# HeatpumpMonitor.net
KiCad netlist of a schematic drawn in EAGLE
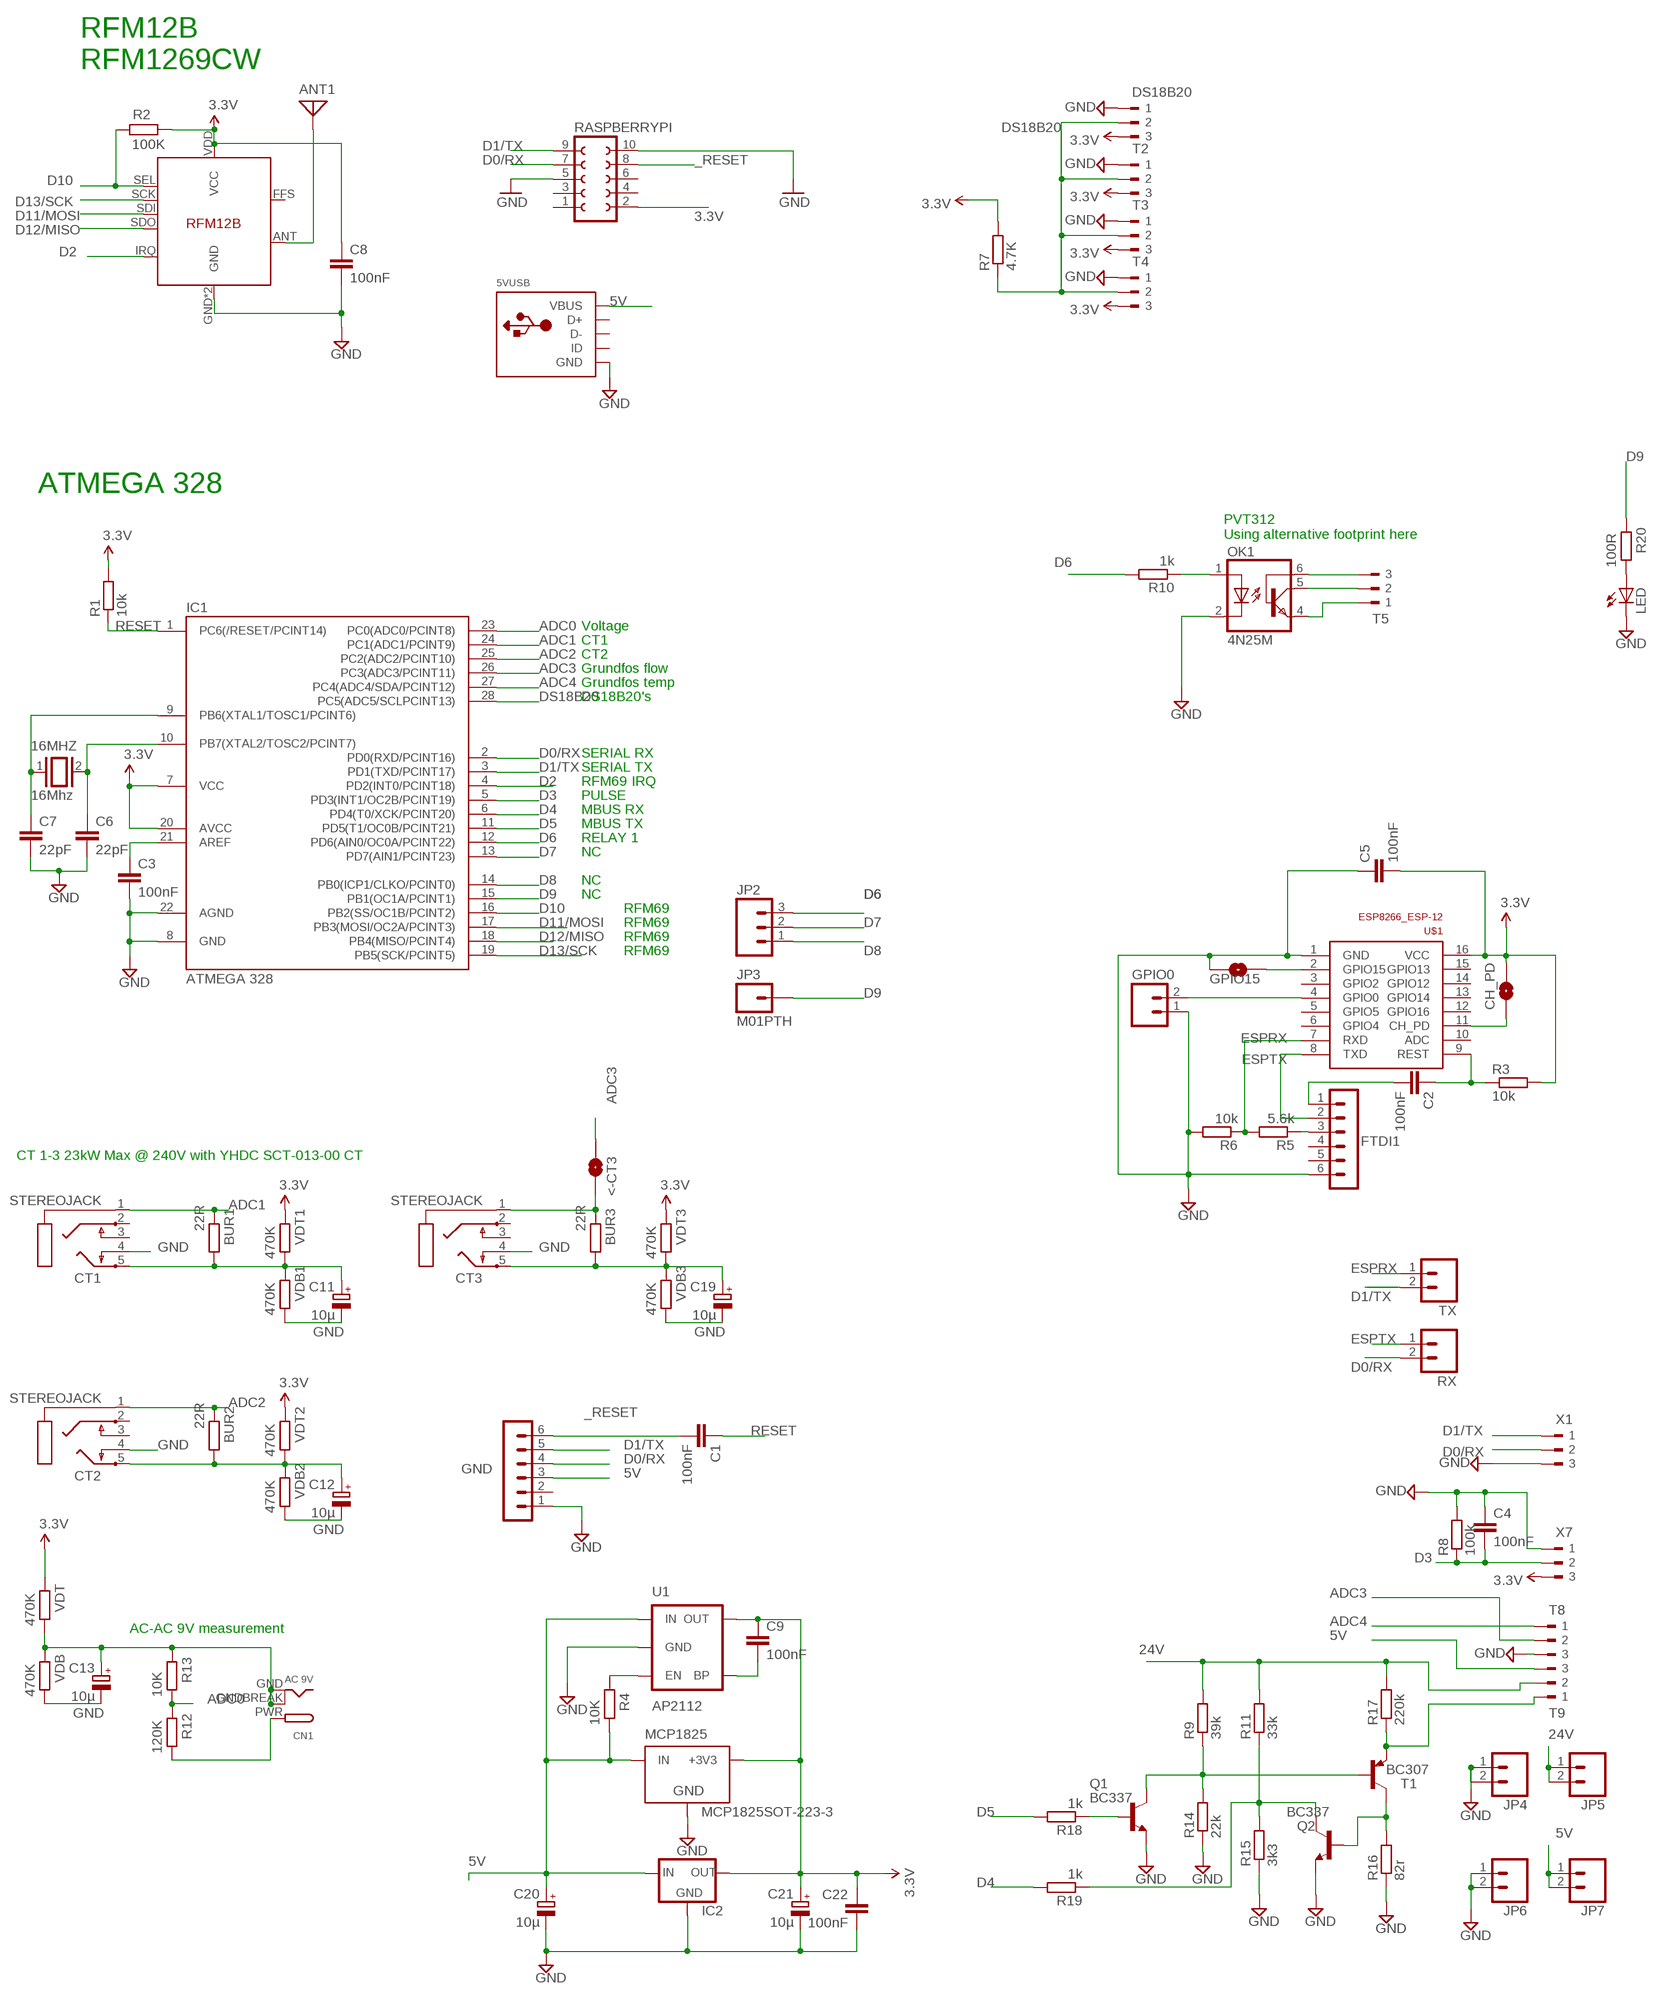
[diagram p0: schematic, sheet 1]

(export (version "E")
  (design (tool "Eeschema 10.0.6"))
  (components
    (comp (ref "5VUSB")
      (value "USBMOLEX")
      (footprint "eagle-import:USB-MINIB-THM-MOLEX")
      (libsource (lib "eagle-import") (part "USBMOLEX"))
    )
    (comp (ref "16MHZ")
      (value "16Mhz")
      (footprint "eagle-import:QS")
      (libsource (lib "eagle-import") (part "XTAL/S"))
    )
    (comp (ref "<-CT3")
      (value "SOLDERJUMPERNO")
      (footprint "eagle-import:SJ_2S-NO")
      (libsource (lib "eagle-import") (part "SOLDERJUMPERNO"))
    )
    (comp (ref "ANT1")
      (value "ANTENNA")
      (footprint "eagle-import:PAD-01")
      (libsource (lib "eagle-import") (part "ANTENNA"))
    )
    (comp (ref "BUR1")
      (value "22R")
      (footprint "eagle-import:0204_7")
      (libsource (lib "eagle-import") (part "R-EU_0204/7"))
    )
    (comp (ref "BUR2")
      (value "22R")
      (footprint "eagle-import:0204_7")
      (libsource (lib "eagle-import") (part "R-EU_0204/7"))
    )
    (comp (ref "BUR3")
      (value "22R")
      (footprint "eagle-import:0204_7")
      (libsource (lib "eagle-import") (part "R-EU_0204/7"))
    )
    (comp (ref "C1")
      (value "100nF")
      (footprint "eagle-import:C025-024X044")
      (libsource (lib "eagle-import") (part "C-EU025-024X044"))
    )
    (comp (ref "C2")
      (value "100nF")
      (footprint "eagle-import:C025-024X044")
      (libsource (lib "eagle-import") (part "C-EU025-024X044"))
    )
    (comp (ref "C3")
      (value "100nF")
      (footprint "eagle-import:C025-024X044")
      (libsource (lib "eagle-import") (part "C-EU025-024X044"))
    )
    (comp (ref "C4")
      (value "100nF")
      (footprint "eagle-import:C025-024X044")
      (libsource (lib "eagle-import") (part "C-EU025-024X044"))
    )
    (comp (ref "C5")
      (value "100nF")
      (footprint "eagle-import:C025-024X044")
      (libsource (lib "eagle-import") (part "C-EU025-024X044"))
    )
    (comp (ref "C6")
      (value "22pF")
      (footprint "eagle-import:C2.5-2")
      (libsource (lib "eagle-import") (part "C2.5/2"))
    )
    (comp (ref "C7")
      (value "22pF")
      (footprint "eagle-import:C2.5-2")
      (libsource (lib "eagle-import") (part "C2.5/2"))
    )
    (comp (ref "C8")
      (value "100nF")
      (footprint "eagle-import:C025-024X044")
      (libsource (lib "eagle-import") (part "C-EU025-024X044"))
    )
    (comp (ref "C9")
      (value "100nF")
      (footprint "eagle-import:C0603")
      (libsource (lib "eagle-import") (part "C-EUC0603"))
    )
    (comp (ref "C11")
      (value "10µ")
      (footprint "eagle-import:E1,8-4")
      (libsource (lib "eagle-import") (part "CPOL-EUE1.8-4"))
    )
    (comp (ref "C12")
      (value "10µ")
      (footprint "eagle-import:E1,8-4")
      (libsource (lib "eagle-import") (part "CPOL-EUE1.8-4"))
    )
    (comp (ref "C13")
      (value "10µ")
      (footprint "eagle-import:E1,8-4")
      (libsource (lib "eagle-import") (part "CPOL-EUE1.8-4"))
    )
    (comp (ref "C19")
      (value "10µ")
      (footprint "eagle-import:E1,8-4")
      (libsource (lib "eagle-import") (part "CPOL-EUE1.8-4"))
    )
    (comp (ref "C20")
      (value "10µ")
      (footprint "eagle-import:E1,8-4")
      (libsource (lib "eagle-import") (part "CPOL-EUE1.8-4"))
    )
    (comp (ref "C21")
      (value "10µ")
      (footprint "eagle-import:E1,8-4")
      (libsource (lib "eagle-import") (part "CPOL-EUE1.8-4"))
    )
    (comp (ref "C22")
      (value "100nF")
      (footprint "eagle-import:C025-024X044")
      (libsource (lib "eagle-import") (part "C-EU025-024X044"))
    )
    (comp (ref "CH_PD")
      (value "SOLDERJUMPERNO")
      (footprint "eagle-import:SJ_2S-NO")
      (libsource (lib "eagle-import") (part "SOLDERJUMPERNO"))
    )
    (comp (ref "CN1")
      (value "AC 9V")
      (footprint "eagle-import:DCJACK_2MM_PTH")
      (libsource (lib "eagle-import") (part "DCBARRELPTH"))
    )
    (comp (ref "CT1")
      (value "STEREOJACK")
      (footprint "eagle-import:STX3100")
      (libsource (lib "eagle-import") (part "STEREOJACK"))
    )
    (comp (ref "CT2")
      (value "STEREOJACK")
      (footprint "eagle-import:STX3100")
      (libsource (lib "eagle-import") (part "STEREOJACK"))
    )
    (comp (ref "CT3")
      (value "STEREOJACK")
      (footprint "eagle-import:STX3100")
      (libsource (lib "eagle-import") (part "STEREOJACK"))
    )
    (comp (ref "DS18B20")
      (value "180-3")
      (footprint "eagle-import:180-3")
      (libsource (lib "eagle-import") (part "180-3"))
    )
    (comp (ref "FTDI1")
      (value "FTDI")
      (footprint "eagle-import:MA06-1")
      (libsource (lib "eagle-import") (part "MA06-1"))
    )
    (comp (ref "GND")
      (value "FTDI")
      (footprint "eagle-import:MA06-1")
      (libsource (lib "eagle-import") (part "MA06-1"))
    )
    (comp (ref "GPIO0")
      (value "M02PTH")
      (footprint "eagle-import:1X02")
      (libsource (lib "eagle-import") (part "M02PTH"))
    )
    (comp (ref "GPIO15")
      (value "SOLDERJUMPERNO")
      (footprint "eagle-import:SJ_2S-NO")
      (libsource (lib "eagle-import") (part "SOLDERJUMPERNO"))
    )
    (comp (ref "IC1")
      (value "ATMEGA 328")
      (footprint "eagle-import:DIL28-3")
      (libsource (lib "eagle-import") (part "ATMEGA48/88/168-PU"))
    )
    (comp (ref "IC2")
      (value "78XXS")
      (footprint "eagle-import:78XXS")
      (libsource (lib "eagle-import") (part "78XXS"))
    )
    (comp (ref "JP2")
      (value "M03PTH")
      (footprint "eagle-import:1X03")
      (libsource (lib "eagle-import") (part "M03PTH"))
    )
    (comp (ref "JP3")
      (value "M01PTH")
      (footprint "eagle-import:1X01")
      (libsource (lib "eagle-import") (part "M01PTH"))
    )
    (comp (ref "JP4")
      (value "M02PTH")
      (footprint "eagle-import:1X02")
      (libsource (lib "eagle-import") (part "M02PTH"))
    )
    (comp (ref "JP5")
      (value "M02PTH")
      (footprint "eagle-import:1X02")
      (libsource (lib "eagle-import") (part "M02PTH"))
    )
    (comp (ref "JP6")
      (value "M02PTH")
      (footprint "eagle-import:1X02")
      (libsource (lib "eagle-import") (part "M02PTH"))
    )
    (comp (ref "JP7")
      (value "M02PTH")
      (footprint "eagle-import:1X02")
      (libsource (lib "eagle-import") (part "M02PTH"))
    )
    (comp (ref "LED")
      (value "LED3MM")
      (footprint "eagle-import:LED3MM")
      (libsource (lib "eagle-import") (part "LED3MM"))
    )
    (comp (ref "MCP1825")
      (value "MCP1825SOT-223-3")
      (footprint "eagle-import:SOT-223")
      (libsource (lib "eagle-import") (part "MCP1825SOT-223-3"))
    )
    (comp (ref "OK1")
      (value "4N25M")
      (footprint "eagle-import:DIL06")
      (fields (field (name "MPN") "4N25-M"))
      (libsource (lib "eagle-import") (part "4N?M25"))
    )
    (comp (ref "Q1")
      (value "BC337")
      (footprint "eagle-import:TO92")
      (libsource (lib "eagle-import") (part "BC337"))
    )
    (comp (ref "Q2")
      (value "BC337")
      (footprint "eagle-import:TO92")
      (libsource (lib "eagle-import") (part "BC337"))
    )
    (comp (ref "R1")
      (value "10k")
      (footprint "eagle-import:0204_7")
      (libsource (lib "eagle-import") (part "resistor_R-EU_0204/7"))
    )
    (comp (ref "R2")
      (value "100K")
      (footprint "eagle-import:0204_7")
      (libsource (lib "eagle-import") (part "R-EU_0204/7"))
    )
    (comp (ref "R3")
      (value "10k")
      (footprint "eagle-import:0204_7")
      (libsource (lib "eagle-import") (part "R-EU_0204/7"))
    )
    (comp (ref "R4")
      (value "10K")
      (footprint "eagle-import:R0603")
      (libsource (lib "eagle-import") (part "R-EU_R0603"))
    )
    (comp (ref "R5")
      (value "5.6k")
      (footprint "eagle-import:0204_7")
      (libsource (lib "eagle-import") (part "R-EU_0204/7"))
    )
    (comp (ref "R6")
      (value "10k")
      (footprint "eagle-import:0204_7")
      (libsource (lib "eagle-import") (part "R-EU_0204/7"))
    )
    (comp (ref "R7")
      (value "4.7K")
      (footprint "eagle-import:0204_7")
      (libsource (lib "eagle-import") (part "resistor_R-EU_0204/7"))
    )
    (comp (ref "R8")
      (value "100k")
      (footprint "eagle-import:0207_2V")
      (libsource (lib "eagle-import") (part "R-EU_0207/2V"))
    )
    (comp (ref "R9")
      (value "39k")
      (footprint "eagle-import:0204_7")
      (libsource (lib "eagle-import") (part "resistor_R-EU_0204/7"))
    )
    (comp (ref "R10")
      (value "1k")
      (footprint "eagle-import:0204_7")
      (libsource (lib "eagle-import") (part "R-EU_0204/7"))
    )
    (comp (ref "R11")
      (value "33k")
      (footprint "eagle-import:0204_7")
      (libsource (lib "eagle-import") (part "resistor_R-EU_0204/7"))
    )
    (comp (ref "R12")
      (value "120K")
      (footprint "eagle-import:0204_7")
      (libsource (lib "eagle-import") (part "R-EU_0204/7"))
    )
    (comp (ref "R13")
      (value "10K")
      (footprint "eagle-import:0204_7")
      (libsource (lib "eagle-import") (part "R-EU_0204/7"))
    )
    (comp (ref "R14")
      (value "22k")
      (footprint "eagle-import:0204_7")
      (libsource (lib "eagle-import") (part "resistor_R-EU_0204/7"))
    )
    (comp (ref "R15")
      (value "3k3")
      (footprint "eagle-import:0204_7")
      (libsource (lib "eagle-import") (part "resistor_R-EU_0204/7"))
    )
    (comp (ref "R16")
      (value "82r")
      (footprint "eagle-import:0204_7")
      (libsource (lib "eagle-import") (part "resistor_R-EU_0204/7"))
    )
    (comp (ref "R17")
      (value "220k")
      (footprint "eagle-import:0204_7")
      (libsource (lib "eagle-import") (part "resistor_R-EU_0204/7"))
    )
    (comp (ref "R18")
      (value "1k")
      (footprint "eagle-import:0204_7")
      (libsource (lib "eagle-import") (part "resistor_R-EU_0204/7"))
    )
    (comp (ref "R19")
      (value "1k")
      (footprint "eagle-import:0204_7")
      (libsource (lib "eagle-import") (part "resistor_R-EU_0204/7"))
    )
    (comp (ref "R20")
      (value "100R")
      (footprint "eagle-import:0204_7")
      (libsource (lib "eagle-import") (part "R-EU_0204/7"))
    )
    (comp (ref "RASPBERRYPI")
      (value "FE05-2")
      (footprint "eagle-import:FE05-2")
      (libsource (lib "eagle-import") (part "FE05-2"))
    )
    (comp (ref "RX")
      (value "M02PTH")
      (footprint "eagle-import:1X02")
      (libsource (lib "eagle-import") (part "M02PTH"))
    )
    (comp (ref "T1")
      (value "BC307")
      (footprint "eagle-import:TO92")
      (libsource (lib "eagle-import") (part "BC307"))
    )
    (comp (ref "T2")
      (value "180-3")
      (footprint "eagle-import:180-3")
      (libsource (lib "eagle-import") (part "180-3"))
    )
    (comp (ref "T3")
      (value "180-3")
      (footprint "eagle-import:180-3")
      (libsource (lib "eagle-import") (part "180-3"))
    )
    (comp (ref "T4")
      (value "180-3")
      (footprint "eagle-import:180-3")
      (libsource (lib "eagle-import") (part "180-3"))
    )
    (comp (ref "T5")
      (value "180-3")
      (footprint "eagle-import:180-3")
      (libsource (lib "eagle-import") (part "180-3"))
    )
    (comp (ref "T8")
      (value "180-3")
      (footprint "eagle-import:180-3")
      (libsource (lib "eagle-import") (part "180-3"))
    )
    (comp (ref "T9")
      (value "180-3")
      (footprint "eagle-import:180-3")
      (libsource (lib "eagle-import") (part "180-3"))
    )
    (comp (ref "TX")
      (value "M02PTH")
      (footprint "eagle-import:1X02")
      (libsource (lib "eagle-import") (part "M02PTH"))
    )
    (comp (ref "U$1")
      (value "ESP8266_ESP-12")
      (footprint "eagle-import:ESP8266-ESP12")
      (libsource (lib "eagle-import") (part "ESP8266_ESP-12"))
    )
    (comp (ref "U$14")
      (value "RFM12B")
      (footprint "eagle-import:RFM12B")
      (libsource (lib "eagle-import") (part "RFM12B"))
    )
    (comp (ref "U1")
      (value "AP2112")
      (footprint "eagle-import:SOT23-5")
      (libsource (lib "eagle-import") (part "V_REG_LDOSMD"))
    )
    (comp (ref "VDB")
      (value "470K")
      (footprint "eagle-import:0204_7")
      (libsource (lib "eagle-import") (part "R-EU_0204/7"))
    )
    (comp (ref "VDB1")
      (value "470K")
      (footprint "eagle-import:0204_7")
      (libsource (lib "eagle-import") (part "R-EU_0204/7"))
    )
    (comp (ref "VDB2")
      (value "470K")
      (footprint "eagle-import:0204_7")
      (libsource (lib "eagle-import") (part "R-EU_0204/7"))
    )
    (comp (ref "VDB3")
      (value "470K")
      (footprint "eagle-import:0204_7")
      (libsource (lib "eagle-import") (part "R-EU_0204/7"))
    )
    (comp (ref "VDT")
      (value "470K")
      (footprint "eagle-import:0204_7")
      (libsource (lib "eagle-import") (part "R-EU_0204/7"))
    )
    (comp (ref "VDT1")
      (value "470K")
      (footprint "eagle-import:0204_7")
      (libsource (lib "eagle-import") (part "R-EU_0204/7"))
    )
    (comp (ref "VDT2")
      (value "470K")
      (footprint "eagle-import:0204_7")
      (libsource (lib "eagle-import") (part "R-EU_0204/7"))
    )
    (comp (ref "VDT3")
      (value "470K")
      (footprint "eagle-import:0204_7")
      (libsource (lib "eagle-import") (part "R-EU_0204/7"))
    )
    (comp (ref "X1")
      (value "180-3")
      (footprint "eagle-import:180-3")
      (libsource (lib "eagle-import") (part "180-3"))
    )
    (comp (ref "X7")
      (value "180-3")
      (footprint "eagle-import:180-3")
      (libsource (lib "eagle-import") (part "180-3"))
    )
  )
  (nets
    (net (code "1") (name "/5V") (class "Default")
      (node (ref "5VUSB") (pin "VBUS") (pinfunction "VBUS_VBUS") (pintype "power_in"))
      (node (ref "C20") (pin "+") (pinfunction "+_+") (pintype "passive"))
      (node (ref "GND") (pin "3") (pinfunction "3_3") (pintype "passive"))
      (node (ref "IC2") (pin "IN") (pinfunction "IN_IN") (pintype "input"))
      (node (ref "JP7") (pin "1") (pinfunction "1_1") (pintype "passive"))
      (node (ref "JP7") (pin "2") (pinfunction "2_2") (pintype "passive"))
      (node (ref "MCP1825") (pin "1") (pinfunction "IN_1") (pintype "power_in"))
      (node (ref "R4") (pin "1") (pinfunction "1_1") (pintype "passive"))
      (node (ref "T9") (pin "3") (pinfunction "3_3") (pintype "passive"))
      (node (ref "U1") (pin "1") (pinfunction "IN_1") (pintype "input"))
    )
    (net (code "2") (name "/24V") (class "Default")
      (node (ref "JP5") (pin "1") (pinfunction "1_1") (pintype "passive"))
      (node (ref "JP5") (pin "2") (pinfunction "2_2") (pintype "passive"))
      (node (ref "R11") (pin "2") (pinfunction "2_2") (pintype "passive"))
      (node (ref "R17") (pin "2") (pinfunction "2_2") (pintype "passive"))
      (node (ref "R9") (pin "2") (pinfunction "2_2") (pintype "passive"))
      (node (ref "T9") (pin "2") (pinfunction "2_2") (pintype "passive"))
    )
    (net (code "3") (name "/ADC0") (class "Default")
      (node (ref "IC1") (pin "23") (pinfunction "PC0(ADC0/PCINT8)_23") (pintype "bidirectional"))
      (node (ref "R12") (pin "2") (pinfunction "2_2") (pintype "passive"))
      (node (ref "R13") (pin "1") (pinfunction "1_1") (pintype "passive"))
    )
    (net (code "4") (name "/ADC1") (class "Default")
      (node (ref "BUR1") (pin "2") (pinfunction "2_2") (pintype "passive"))
      (node (ref "CT1") (pin "1") (pinfunction "1_1") (pintype "passive"))
      (node (ref "IC1") (pin "24") (pinfunction "PC1(ADC1/PCINT9)_24") (pintype "bidirectional"))
    )
    (net (code "5") (name "/ADC2") (class "Default")
      (node (ref "BUR2") (pin "2") (pinfunction "2_2") (pintype "passive"))
      (node (ref "CT2") (pin "1") (pinfunction "1_1") (pintype "passive"))
      (node (ref "IC1") (pin "25") (pinfunction "PC2(ADC2/PCINT10)_25") (pintype "bidirectional"))
    )
    (net (code "6") (name "/ADC3") (class "Default")
      (node (ref "<-CT3") (pin "2") (pinfunction "2_2") (pintype "passive"))
      (node (ref "IC1") (pin "26") (pinfunction "PC3(ADC3/PCINT11)_26") (pintype "bidirectional"))
      (node (ref "T8") (pin "2") (pinfunction "2_2") (pintype "passive"))
    )
    (net (code "7") (name "/ADC4") (class "Default")
      (node (ref "IC1") (pin "27") (pinfunction "PC4(ADC4/SDA/PCINT12)_27") (pintype "bidirectional"))
      (node (ref "T8") (pin "1") (pinfunction "1_1") (pintype "passive"))
    )
    (net (code "8") (name "/D0{slash}RX") (class "Default")
      (node (ref "GND") (pin "4") (pinfunction "4_4") (pintype "passive"))
      (node (ref "IC1") (pin "2") (pinfunction "PD0(RXD/PCINT16)_2") (pintype "bidirectional"))
      (node (ref "RASPBERRYPI") (pin "7") (pinfunction "7_7") (pintype "passive"))
      (node (ref "RX") (pin "2") (pinfunction "2_2") (pintype "passive"))
      (node (ref "X1") (pin "2") (pinfunction "2_2") (pintype "passive"))
    )
    (net (code "9") (name "/D1{slash}TX") (class "Default")
      (node (ref "GND") (pin "5") (pinfunction "5_5") (pintype "passive"))
      (node (ref "IC1") (pin "3") (pinfunction "PD1(TXD/PCINT17)_3") (pintype "bidirectional"))
      (node (ref "RASPBERRYPI") (pin "9") (pinfunction "9_9") (pintype "passive"))
      (node (ref "TX") (pin "2") (pinfunction "2_2") (pintype "passive"))
      (node (ref "X1") (pin "1") (pinfunction "1_1") (pintype "passive"))
    )
    (net (code "10") (name "/D2") (class "Default")
      (node (ref "IC1") (pin "4") (pinfunction "PD2(INT0/PCINT18)_4") (pintype "bidirectional"))
      (node (ref "U$14") (pin "IRQ") (pinfunction "IRQ_IRQ") (pintype "open_collector"))
    )
    (net (code "11") (name "/D3") (class "Default")
      (node (ref "C4") (pin "2") (pinfunction "2_2") (pintype "passive"))
      (node (ref "IC1") (pin "5") (pinfunction "PD3(INT1/OC2B/PCINT19)_5") (pintype "bidirectional"))
      (node (ref "R8") (pin "1") (pinfunction "1_1") (pintype "passive"))
      (node (ref "X7") (pin "2") (pinfunction "2_2") (pintype "passive"))
    )
    (net (code "12") (name "/D4") (class "Default")
      (node (ref "IC1") (pin "6") (pinfunction "PD4(T0/XCK/PCINT20)_6") (pintype "bidirectional"))
      (node (ref "R19") (pin "2") (pinfunction "2_2") (pintype "passive"))
    )
    (net (code "13") (name "/D5") (class "Default")
      (node (ref "IC1") (pin "11") (pinfunction "PD5(T1/OC0B/PCINT21)_11") (pintype "bidirectional"))
      (node (ref "R18") (pin "2") (pinfunction "2_2") (pintype "passive"))
    )
    (net (code "14") (name "/D6") (class "Default")
      (node (ref "IC1") (pin "12") (pinfunction "PD6(AIN0/OC0A/PCINT22)_12") (pintype "bidirectional"))
      (node (ref "JP2") (pin "3") (pinfunction "3_3") (pintype "passive"))
      (node (ref "R10") (pin "2") (pinfunction "2_2") (pintype "passive"))
    )
    (net (code "15") (name "/D7") (class "Default")
      (node (ref "IC1") (pin "13") (pinfunction "PD7(AIN1/PCINT23)_13") (pintype "bidirectional"))
      (node (ref "JP2") (pin "2") (pinfunction "2_2") (pintype "passive"))
    )
    (net (code "16") (name "/D8") (class "Default")
      (node (ref "IC1") (pin "14") (pinfunction "PB0(ICP1/CLKO/PCINT0)_14") (pintype "bidirectional"))
      (node (ref "JP2") (pin "1") (pinfunction "1_1") (pintype "passive"))
    )
    (net (code "17") (name "/D9") (class "Default")
      (node (ref "IC1") (pin "15") (pinfunction "PB1(OC1A/PCINT1)_15") (pintype "bidirectional"))
      (node (ref "JP3") (pin "1") (pinfunction "1_1") (pintype "passive"))
      (node (ref "R20") (pin "2") (pinfunction "2_2") (pintype "passive"))
    )
    (net (code "18") (name "/D10") (class "Default")
      (node (ref "IC1") (pin "16") (pinfunction "PB2(SS/OC1B/PCINT2)_16") (pintype "bidirectional"))
      (node (ref "R2") (pin "2") (pinfunction "2_2") (pintype "passive"))
      (node (ref "U$14") (pin "SEL") (pinfunction "SEL_SEL") (pintype "input"))
    )
    (net (code "19") (name "/D11{slash}MOSI") (class "Default")
      (node (ref "IC1") (pin "17") (pinfunction "PB3(MOSI/OC2A/PCINT3)_17") (pintype "bidirectional"))
      (node (ref "U$14") (pin "SDI") (pinfunction "SDI_SDI") (pintype "input"))
    )
    (net (code "20") (name "/D12{slash}MISO") (class "Default")
      (node (ref "IC1") (pin "18") (pinfunction "PB4(MISO/PCINT4)_18") (pintype "bidirectional"))
      (node (ref "U$14") (pin "SDO") (pinfunction "SDO_SDO") (pintype "output"))
    )
    (net (code "21") (name "/D13{slash}SCK") (class "Default")
      (node (ref "IC1") (pin "19") (pinfunction "PB5(SCK/PCINT5)_19") (pintype "bidirectional"))
      (node (ref "U$14") (pin "SCK") (pinfunction "SCK_SCK") (pintype "input"))
    )
    (net (code "22") (name "/DS18B20") (class "Default")
      (node (ref "DS18B20") (pin "2") (pinfunction "2_2") (pintype "passive"))
      (node (ref "IC1") (pin "28") (pinfunction "PC5(ADC5/SCLPCINT13)_28") (pintype "bidirectional"))
      (node (ref "R7") (pin "1") (pinfunction "1_1") (pintype "passive"))
      (node (ref "T2") (pin "2") (pinfunction "2_2") (pintype "passive"))
      (node (ref "T3") (pin "2") (pinfunction "2_2") (pintype "passive"))
      (node (ref "T4") (pin "2") (pinfunction "2_2") (pintype "passive"))
    )
    (net (code "23") (name "/ESPRX") (class "Default")
      (node (ref "R5") (pin "2") (pinfunction "2_2") (pintype "passive"))
      (node (ref "R6") (pin "1") (pinfunction "1_1") (pintype "passive"))
      (node (ref "TX") (pin "1") (pinfunction "1_1") (pintype "passive"))
      (node (ref "U$1") (pin "7") (pinfunction "RXD_7") (pintype "bidirectional"))
    )
    (net (code "24") (name "/ESPTX") (class "Default")
      (node (ref "FTDI1") (pin "2") (pinfunction "2_2") (pintype "passive"))
      (node (ref "RX") (pin "1") (pinfunction "1_1") (pintype "passive"))
      (node (ref "U$1") (pin "8") (pinfunction "TXD_8") (pintype "bidirectional"))
    )
    (net (code "25") (name "/RESET") (class "Default")
      (node (ref "C1") (pin "1") (pinfunction "1_1") (pintype "passive"))
      (node (ref "IC1") (pin "1") (pinfunction "PC6(/RESET/PCINT14)_1") (pintype "bidirectional"))
      (node (ref "R1") (pin "1") (pinfunction "1_1") (pintype "passive"))
    )
    (net (code "26") (name "/_RESET") (class "Default")
      (node (ref "C1") (pin "2") (pinfunction "2_2") (pintype "passive"))
      (node (ref "GND") (pin "6") (pinfunction "6_6") (pintype "passive"))
      (node (ref "RASPBERRYPI") (pin "8") (pinfunction "8_8") (pintype "passive"))
    )
    (net (code "27") (name "3.3V") (class "Default")
      (node (ref "C21") (pin "+") (pinfunction "+_+") (pintype "passive"))
      (node (ref "C22") (pin "1") (pinfunction "1_1") (pintype "passive"))
      (node (ref "C5") (pin "2") (pinfunction "2_2") (pintype "passive"))
      (node (ref "C8") (pin "1") (pinfunction "1_1") (pintype "passive"))
      (node (ref "C9") (pin "1") (pinfunction "1_1") (pintype "passive"))
      (node (ref "CH_PD") (pin "1") (pinfunction "1_1") (pintype "passive"))
      (node (ref "DS18B20") (pin "3") (pinfunction "3_3") (pintype "passive"))
      (node (ref "IC1") (pin "20") (pinfunction "AVCC_20") (pintype "passive"))
      (node (ref "IC1") (pin "7") (pinfunction "VCC_7") (pintype "power_in"))
      (node (ref "IC2") (pin "OUT") (pinfunction "OUT_OUT") (pintype "passive"))
      (node (ref "MCP1825") (pin "3") (pinfunction "+3V3_3") (pintype "power_in"))
      (node (ref "R1") (pin "2") (pinfunction "2_2") (pintype "passive"))
      (node (ref "R2") (pin "1") (pinfunction "1_1") (pintype "passive"))
      (node (ref "R3") (pin "2") (pinfunction "2_2") (pintype "passive"))
      (node (ref "R7") (pin "2") (pinfunction "2_2") (pintype "passive"))
      (node (ref "RASPBERRYPI") (pin "2") (pinfunction "2_2") (pintype "passive"))
      (node (ref "T2") (pin "3") (pinfunction "3_3") (pintype "passive"))
      (node (ref "T3") (pin "3") (pinfunction "3_3") (pintype "passive"))
      (node (ref "T4") (pin "3") (pinfunction "3_3") (pintype "passive"))
      (node (ref "U$1") (pin "16") (pinfunction "VCC_16") (pintype "bidirectional"))
      (node (ref "U$14") (pin "VDD") (pinfunction "VCC_VDD") (pintype "power_in"))
      (node (ref "U1") (pin "5") (pinfunction "OUT_5") (pintype "passive"))
      (node (ref "VDT") (pin "2") (pinfunction "2_2") (pintype "passive"))
      (node (ref "VDT1") (pin "2") (pinfunction "2_2") (pintype "passive"))
      (node (ref "VDT2") (pin "2") (pinfunction "2_2") (pintype "passive"))
      (node (ref "VDT3") (pin "2") (pinfunction "2_2") (pintype "passive"))
      (node (ref "X7") (pin "3") (pinfunction "3_3") (pintype "passive"))
    )
    (net (code "28") (name "GND") (class "Default")
      (node (ref "5VUSB") (pin "GND") (pinfunction "GND_GND") (pintype "power_in"))
      (node (ref "C11") (pin "-") (pinfunction "-_-") (pintype "passive"))
      (node (ref "C12") (pin "-") (pinfunction "-_-") (pintype "passive"))
      (node (ref "C13") (pin "-") (pinfunction "-_-") (pintype "passive"))
      (node (ref "C19") (pin "-") (pinfunction "-_-") (pintype "passive"))
      (node (ref "C20") (pin "-") (pinfunction "-_-") (pintype "passive"))
      (node (ref "C21") (pin "-") (pinfunction "-_-") (pintype "passive"))
      (node (ref "C22") (pin "2") (pinfunction "2_2") (pintype "passive"))
      (node (ref "C3") (pin "2") (pinfunction "2_2") (pintype "passive"))
      (node (ref "C4") (pin "1") (pinfunction "1_1") (pintype "passive"))
      (node (ref "C5") (pin "1") (pinfunction "1_1") (pintype "passive"))
      (node (ref "C6") (pin "2") (pinfunction "2_2") (pintype "passive"))
      (node (ref "C7") (pin "2") (pinfunction "2_2") (pintype "passive"))
      (node (ref "C8") (pin "2") (pinfunction "2_2") (pintype "passive"))
      (node (ref "CT1") (pin "4") (pinfunction "4_4") (pintype "passive"))
      (node (ref "CT2") (pin "4") (pinfunction "4_4") (pintype "passive"))
      (node (ref "CT3") (pin "4") (pinfunction "4_4") (pintype "passive"))
      (node (ref "DS18B20") (pin "1") (pinfunction "1_1") (pintype "passive"))
      (node (ref "FTDI1") (pin "6") (pinfunction "6_6") (pintype "passive"))
      (node (ref "GND") (pin "1") (pinfunction "1_1") (pintype "passive"))
      (node (ref "GPIO0") (pin "1") (pinfunction "1_1") (pintype "passive"))
      (node (ref "GPIO15") (pin "2") (pinfunction "2_2") (pintype "passive"))
      (node (ref "IC1") (pin "22") (pinfunction "AGND_22") (pintype "power_in"))
      (node (ref "IC1") (pin "8") (pinfunction "GND_8") (pintype "power_in"))
      (node (ref "IC2") (pin "GND") (pinfunction "GND_GND") (pintype "input"))
      (node (ref "JP4") (pin "1") (pinfunction "1_1") (pintype "passive"))
      (node (ref "JP4") (pin "2") (pinfunction "2_2") (pintype "passive"))
      (node (ref "JP6") (pin "1") (pinfunction "1_1") (pintype "passive"))
      (node (ref "JP6") (pin "2") (pinfunction "2_2") (pintype "passive"))
      (node (ref "LED") (pin "K") (pinfunction "C_K") (pintype "passive"))
      (node (ref "MCP1825") (pin "2") (pinfunction "GND_2") (pintype "power_in"))
      (node (ref "OK1") (pin "2") (pinfunction "C_2") (pintype "passive"))
      (node (ref "Q1") (pin "1") (pinfunction "E_1") (pintype "passive"))
      (node (ref "Q2") (pin "1") (pinfunction "E_1") (pintype "passive"))
      (node (ref "R14") (pin "1") (pinfunction "1_1") (pintype "passive"))
      (node (ref "R15") (pin "1") (pinfunction "1_1") (pintype "passive"))
      (node (ref "R16") (pin "1") (pinfunction "1_1") (pintype "passive"))
      (node (ref "R6") (pin "2") (pinfunction "2_2") (pintype "passive"))
      (node (ref "R8") (pin "2") (pinfunction "2_2") (pintype "passive"))
      (node (ref "RASPBERRYPI") (pin "10") (pinfunction "10_10") (pintype "passive"))
      (node (ref "RASPBERRYPI") (pin "5") (pinfunction "5_5") (pintype "passive"))
      (node (ref "T2") (pin "1") (pinfunction "1_1") (pintype "passive"))
      (node (ref "T3") (pin "1") (pinfunction "1_1") (pintype "passive"))
      (node (ref "T4") (pin "1") (pinfunction "1_1") (pintype "passive"))
      (node (ref "T8") (pin "3") (pinfunction "3_3") (pintype "passive"))
      (node (ref "U$1") (pin "1") (pinfunction "GND_1") (pintype "bidirectional"))
      (node (ref "U$14") (pin "GND") (pinfunction "GND_GND") (pintype "power_in"))
      (node (ref "U$14") (pin "P$12") (pinfunction "GND_P$12") (pintype "power_in"))
      (node (ref "U1") (pin "2") (pinfunction "GND_2") (pintype "input"))
      (node (ref "VDB") (pin "1") (pinfunction "1_1") (pintype "passive"))
      (node (ref "VDB1") (pin "1") (pinfunction "1_1") (pintype "passive"))
      (node (ref "VDB2") (pin "1") (pinfunction "1_1") (pintype "passive"))
      (node (ref "VDB3") (pin "1") (pinfunction "1_1") (pintype "passive"))
      (node (ref "X1") (pin "3") (pinfunction "3_3") (pintype "passive"))
      (node (ref "X7") (pin "1") (pinfunction "1_1") (pintype "passive"))
    )
    (net (code "29") (name "Net-(<-CT3-Pad1)") (class "Default")
      (node (ref "<-CT3") (pin "1") (pinfunction "1_1") (pintype "passive"))
      (node (ref "BUR3") (pin "2") (pinfunction "2_2") (pintype "passive"))
      (node (ref "CT3") (pin "1") (pinfunction "1_1") (pintype "passive"))
    )
    (net (code "30") (name "Net-(ANT1-Pad1)") (class "Default")
      (node (ref "ANT1") (pin "1") (pinfunction "1_1") (pintype "output"))
      (node (ref "U$14") (pin "ANT") (pinfunction "ANT_ANT") (pintype "passive"))
    )
    (net (code "31") (name "Net-(BUR1-Pad1)") (class "Default")
      (node (ref "BUR1") (pin "1") (pinfunction "1_1") (pintype "passive"))
      (node (ref "C11") (pin "+") (pinfunction "+_+") (pintype "passive"))
      (node (ref "CT1") (pin "5") (pinfunction "5_5") (pintype "passive"))
      (node (ref "VDB1") (pin "2") (pinfunction "2_2") (pintype "passive"))
      (node (ref "VDT1") (pin "1") (pinfunction "1_1") (pintype "passive"))
    )
    (net (code "32") (name "Net-(BUR2-Pad1)") (class "Default")
      (node (ref "BUR2") (pin "1") (pinfunction "1_1") (pintype "passive"))
      (node (ref "C12") (pin "+") (pinfunction "+_+") (pintype "passive"))
      (node (ref "CT2") (pin "5") (pinfunction "5_5") (pintype "passive"))
      (node (ref "VDB2") (pin "2") (pinfunction "2_2") (pintype "passive"))
      (node (ref "VDT2") (pin "1") (pinfunction "1_1") (pintype "passive"))
    )
    (net (code "33") (name "Net-(BUR3-Pad1)") (class "Default")
      (node (ref "BUR3") (pin "1") (pinfunction "1_1") (pintype "passive"))
      (node (ref "C19") (pin "+") (pinfunction "+_+") (pintype "passive"))
      (node (ref "CT3") (pin "5") (pinfunction "5_5") (pintype "passive"))
      (node (ref "VDB3") (pin "2") (pinfunction "2_2") (pintype "passive"))
      (node (ref "VDT3") (pin "1") (pinfunction "1_1") (pintype "passive"))
    )
    (net (code "34") (name "Net-(C2-Pad2)") (class "Default")
      (node (ref "C2") (pin "2") (pinfunction "2_2") (pintype "passive"))
      (node (ref "FTDI1") (pin "1") (pinfunction "1_1") (pintype "passive"))
    )
    (net (code "35") (name "Net-(C13-Pad+)") (class "Default")
      (node (ref "C13") (pin "+") (pinfunction "+_+") (pintype "passive"))
      (node (ref "CN1") (pin "GND") (pinfunction "GND_GND") (pintype "power_in"))
      (node (ref "CN1") (pin "GNDBREAK") (pinfunction "GNDBREAK_GNDBREAK") (pintype "power_in"))
      (node (ref "R13") (pin "2") (pinfunction "2_2") (pintype "passive"))
      (node (ref "VDB") (pin "2") (pinfunction "2_2") (pintype "passive"))
      (node (ref "VDT") (pin "1") (pinfunction "1_1") (pintype "passive"))
    )
    (net (code "36") (name "Net-(CN1-PadPWR)") (class "Default")
      (node (ref "CN1") (pin "PWR") (pinfunction "PWR_PWR") (pintype "power_in"))
      (node (ref "R12") (pin "1") (pinfunction "1_1") (pintype "passive"))
    )
    (net (code "37") (name "Net-(FTDI1-Pad3)") (class "Default")
      (node (ref "FTDI1") (pin "3") (pinfunction "3_3") (pintype "passive"))
      (node (ref "R5") (pin "1") (pinfunction "1_1") (pintype "passive"))
    )
    (net (code "38") (name "Net-(IC1-AREF)") (class "Default")
      (node (ref "C3") (pin "1") (pinfunction "1_1") (pintype "passive"))
      (node (ref "IC1") (pin "21") (pinfunction "AREF_21") (pintype "passive"))
    )
    (net (code "39") (name "Net-(IC1-PB6(XTAL1{slash}TOSC1{slash}PCINT6))") (class "Default")
      (node (ref "16MHZ") (pin "1") (pinfunction "1_1") (pintype "passive"))
      (node (ref "C7") (pin "1") (pinfunction "1_1") (pintype "passive"))
      (node (ref "IC1") (pin "9") (pinfunction "PB6(XTAL1/TOSC1/PCINT6)_9") (pintype "bidirectional"))
    )
    (net (code "40") (name "Net-(IC1-PB7(XTAL2{slash}TOSC2{slash}PCINT7))") (class "Default")
      (node (ref "16MHZ") (pin "2") (pinfunction "2_2") (pintype "passive"))
      (node (ref "C6") (pin "1") (pinfunction "1_1") (pintype "passive"))
      (node (ref "IC1") (pin "10") (pinfunction "PB7(XTAL2/TOSC2/PCINT7)_10") (pintype "bidirectional"))
    )
    (net (code "41") (name "Net-(LED-PadA)") (class "Default")
      (node (ref "LED") (pin "A") (pinfunction "A_A") (pintype "passive"))
      (node (ref "R20") (pin "1") (pinfunction "1_1") (pintype "passive"))
    )
    (net (code "42") (name "Net-(OK1-A)") (class "Default")
      (node (ref "OK1") (pin "1") (pinfunction "A_1") (pintype "passive"))
      (node (ref "R10") (pin "1") (pinfunction "1_1") (pintype "passive"))
    )
    (net (code "43") (name "Net-(OK1-BAS)") (class "Default")
      (node (ref "OK1") (pin "6") (pinfunction "BAS_6") (pintype "passive"))
      (node (ref "T5") (pin "3") (pinfunction "3_3") (pintype "passive"))
    )
    (net (code "44") (name "Net-(OK1-COL)") (class "Default")
      (node (ref "OK1") (pin "5") (pinfunction "COL_5") (pintype "passive"))
      (node (ref "T5") (pin "2") (pinfunction "2_2") (pintype "passive"))
    )
    (net (code "45") (name "Net-(OK1-EMI)") (class "Default")
      (node (ref "OK1") (pin "4") (pinfunction "EMI_4") (pintype "passive"))
      (node (ref "T5") (pin "1") (pinfunction "1_1") (pintype "passive"))
    )
    (net (code "46") (name "Net-(Q1-B)") (class "Default")
      (node (ref "Q1") (pin "2") (pinfunction "B_2") (pintype "passive"))
      (node (ref "R18") (pin "1") (pinfunction "1_1") (pintype "passive"))
    )
    (net (code "47") (name "Net-(Q1-C)") (class "Default")
      (node (ref "Q1") (pin "3") (pinfunction "C_3") (pintype "passive"))
      (node (ref "R14") (pin "2") (pinfunction "2_2") (pintype "passive"))
      (node (ref "R9") (pin "1") (pinfunction "1_1") (pintype "passive"))
      (node (ref "T1") (pin "2") (pinfunction "B_2") (pintype "passive"))
    )
    (net (code "48") (name "Net-(Q2-B)") (class "Default")
      (node (ref "Q2") (pin "2") (pinfunction "B_2") (pintype "passive"))
      (node (ref "R16") (pin "2") (pinfunction "2_2") (pintype "passive"))
      (node (ref "T1") (pin "3") (pinfunction "C_3") (pintype "passive"))
    )
    (net (code "49") (name "Net-(Q2-C)") (class "Default")
      (node (ref "Q2") (pin "3") (pinfunction "C_3") (pintype "passive"))
      (node (ref "R11") (pin "1") (pinfunction "1_1") (pintype "passive"))
      (node (ref "R15") (pin "2") (pinfunction "2_2") (pintype "passive"))
      (node (ref "R19") (pin "1") (pinfunction "1_1") (pintype "passive"))
    )
    (net (code "50") (name "Net-(T1-E)") (class "Default")
      (node (ref "R17") (pin "1") (pinfunction "1_1") (pintype "passive"))
      (node (ref "T1") (pin "1") (pinfunction "E_1") (pintype "passive"))
      (node (ref "T9") (pin "1") (pinfunction "1_1") (pintype "passive"))
    )
    (net (code "51") (name "Net-(U$1-CH_PD)") (class "Default")
      (node (ref "CH_PD") (pin "2") (pinfunction "2_2") (pintype "passive"))
      (node (ref "U$1") (pin "11") (pinfunction "CH_PD_11") (pintype "bidirectional"))
    )
    (net (code "52") (name "Net-(U$1-GPIO0)") (class "Default")
      (node (ref "GPIO0") (pin "2") (pinfunction "2_2") (pintype "passive"))
      (node (ref "U$1") (pin "4") (pinfunction "GPIO0_4") (pintype "bidirectional"))
    )
    (net (code "53") (name "Net-(U$1-GPIO15)") (class "Default")
      (node (ref "GPIO15") (pin "1") (pinfunction "1_1") (pintype "passive"))
      (node (ref "U$1") (pin "2") (pinfunction "GPIO15_2") (pintype "bidirectional"))
    )
    (net (code "54") (name "Net-(U$1-REST)") (class "Default")
      (node (ref "C2") (pin "1") (pinfunction "1_1") (pintype "passive"))
      (node (ref "R3") (pin "1") (pinfunction "1_1") (pintype "passive"))
      (node (ref "U$1") (pin "9") (pinfunction "REST_9") (pintype "bidirectional"))
    )
    (net (code "55") (name "Net-(U1-BP)") (class "Default")
      (node (ref "C9") (pin "2") (pinfunction "2_2") (pintype "passive"))
      (node (ref "U1") (pin "4") (pinfunction "BP_4") (pintype "input"))
    )
    (net (code "56") (name "Net-(U1-EN)") (class "Default")
      (node (ref "R4") (pin "2") (pinfunction "2_2") (pintype "passive"))
      (node (ref "U1") (pin "3") (pinfunction "EN_3") (pintype "input"))
    )
    (net (code "57") (name "unconnected-(5VUSB-PadD+)") (class "Default")
      (node (ref "5VUSB") (pin "D+") (pinfunction "D+_D+") (pintype "bidirectional"))
    )
    (net (code "58") (name "unconnected-(5VUSB-PadD-)") (class "Default")
      (node (ref "5VUSB") (pin "D-") (pinfunction "D-_D-") (pintype "bidirectional"))
    )
    (net (code "59") (name "unconnected-(5VUSB-PadID)") (class "Default")
      (node (ref "5VUSB") (pin "ID") (pinfunction "ID_ID") (pintype "bidirectional"))
    )
    (net (code "60") (name "unconnected-(CT1-Pad2)") (class "Default")
      (node (ref "CT1") (pin "2") (pinfunction "2_2") (pintype "passive"))
    )
    (net (code "61") (name "unconnected-(CT1-Pad3)") (class "Default")
      (node (ref "CT1") (pin "3") (pinfunction "3_3") (pintype "passive"))
    )
    (net (code "62") (name "unconnected-(CT2-Pad2)") (class "Default")
      (node (ref "CT2") (pin "2") (pinfunction "2_2") (pintype "passive"))
    )
    (net (code "63") (name "unconnected-(CT2-Pad3)") (class "Default")
      (node (ref "CT2") (pin "3") (pinfunction "3_3") (pintype "passive"))
    )
    (net (code "64") (name "unconnected-(CT3-Pad2)") (class "Default")
      (node (ref "CT3") (pin "2") (pinfunction "2_2") (pintype "passive"))
    )
    (net (code "65") (name "unconnected-(CT3-Pad3)") (class "Default")
      (node (ref "CT3") (pin "3") (pinfunction "3_3") (pintype "passive"))
    )
    (net (code "66") (name "unconnected-(FTDI1-Pad4)") (class "Default")
      (node (ref "FTDI1") (pin "4") (pinfunction "4_4") (pintype "passive"))
    )
    (net (code "67") (name "unconnected-(FTDI1-Pad5)") (class "Default")
      (node (ref "FTDI1") (pin "5") (pinfunction "5_5") (pintype "passive"))
    )
    (net (code "68") (name "unconnected-(GND-Pad2)") (class "Default")
      (node (ref "GND") (pin "2") (pinfunction "2_2") (pintype "passive"))
    )
    (net (code "69") (name "unconnected-(RASPBERRYPI-Pad1)") (class "Default")
      (node (ref "RASPBERRYPI") (pin "1") (pinfunction "1_1") (pintype "passive"))
    )
    (net (code "70") (name "unconnected-(RASPBERRYPI-Pad3)") (class "Default")
      (node (ref "RASPBERRYPI") (pin "3") (pinfunction "3_3") (pintype "passive"))
    )
    (net (code "71") (name "unconnected-(RASPBERRYPI-Pad4)") (class "Default")
      (node (ref "RASPBERRYPI") (pin "4") (pinfunction "4_4") (pintype "passive"))
    )
    (net (code "72") (name "unconnected-(RASPBERRYPI-Pad6)") (class "Default")
      (node (ref "RASPBERRYPI") (pin "6") (pinfunction "6_6") (pintype "passive"))
    )
    (net (code "73") (name "unconnected-(U$1-ADC-Pad10)") (class "Default")
      (node (ref "U$1") (pin "10") (pinfunction "ADC_10") (pintype "bidirectional"))
    )
    (net (code "74") (name "unconnected-(U$1-GPIO2-Pad3)") (class "Default")
      (node (ref "U$1") (pin "3") (pinfunction "GPIO2_3") (pintype "bidirectional"))
    )
    (net (code "75") (name "unconnected-(U$1-GPIO4-Pad6)") (class "Default")
      (node (ref "U$1") (pin "6") (pinfunction "GPIO4_6") (pintype "bidirectional"))
    )
    (net (code "76") (name "unconnected-(U$1-GPIO5-Pad5)") (class "Default")
      (node (ref "U$1") (pin "5") (pinfunction "GPIO5_5") (pintype "bidirectional"))
    )
    (net (code "77") (name "unconnected-(U$1-GPIO12-Pad14)") (class "Default")
      (node (ref "U$1") (pin "14") (pinfunction "GPIO12_14") (pintype "bidirectional"))
    )
    (net (code "78") (name "unconnected-(U$1-GPIO13-Pad15)") (class "Default")
      (node (ref "U$1") (pin "15") (pinfunction "GPIO13_15") (pintype "bidirectional"))
    )
    (net (code "79") (name "unconnected-(U$1-GPIO14-Pad13)") (class "Default")
      (node (ref "U$1") (pin "13") (pinfunction "GPIO14_13") (pintype "bidirectional"))
    )
    (net (code "80") (name "unconnected-(U$1-GPIO16-Pad12)") (class "Default")
      (node (ref "U$1") (pin "12") (pinfunction "GPIO16_12") (pintype "bidirectional"))
    )
    (net (code "81") (name "unconnected-(U$14-PadFFS)") (class "Default")
      (node (ref "U$14") (pin "FFS") (pinfunction "FFS_FFS") (pintype "bidirectional"))
    )
  )
)
